# cable_with_five_imu.net
KiCad netlist of a schematic drawn in EAGLE
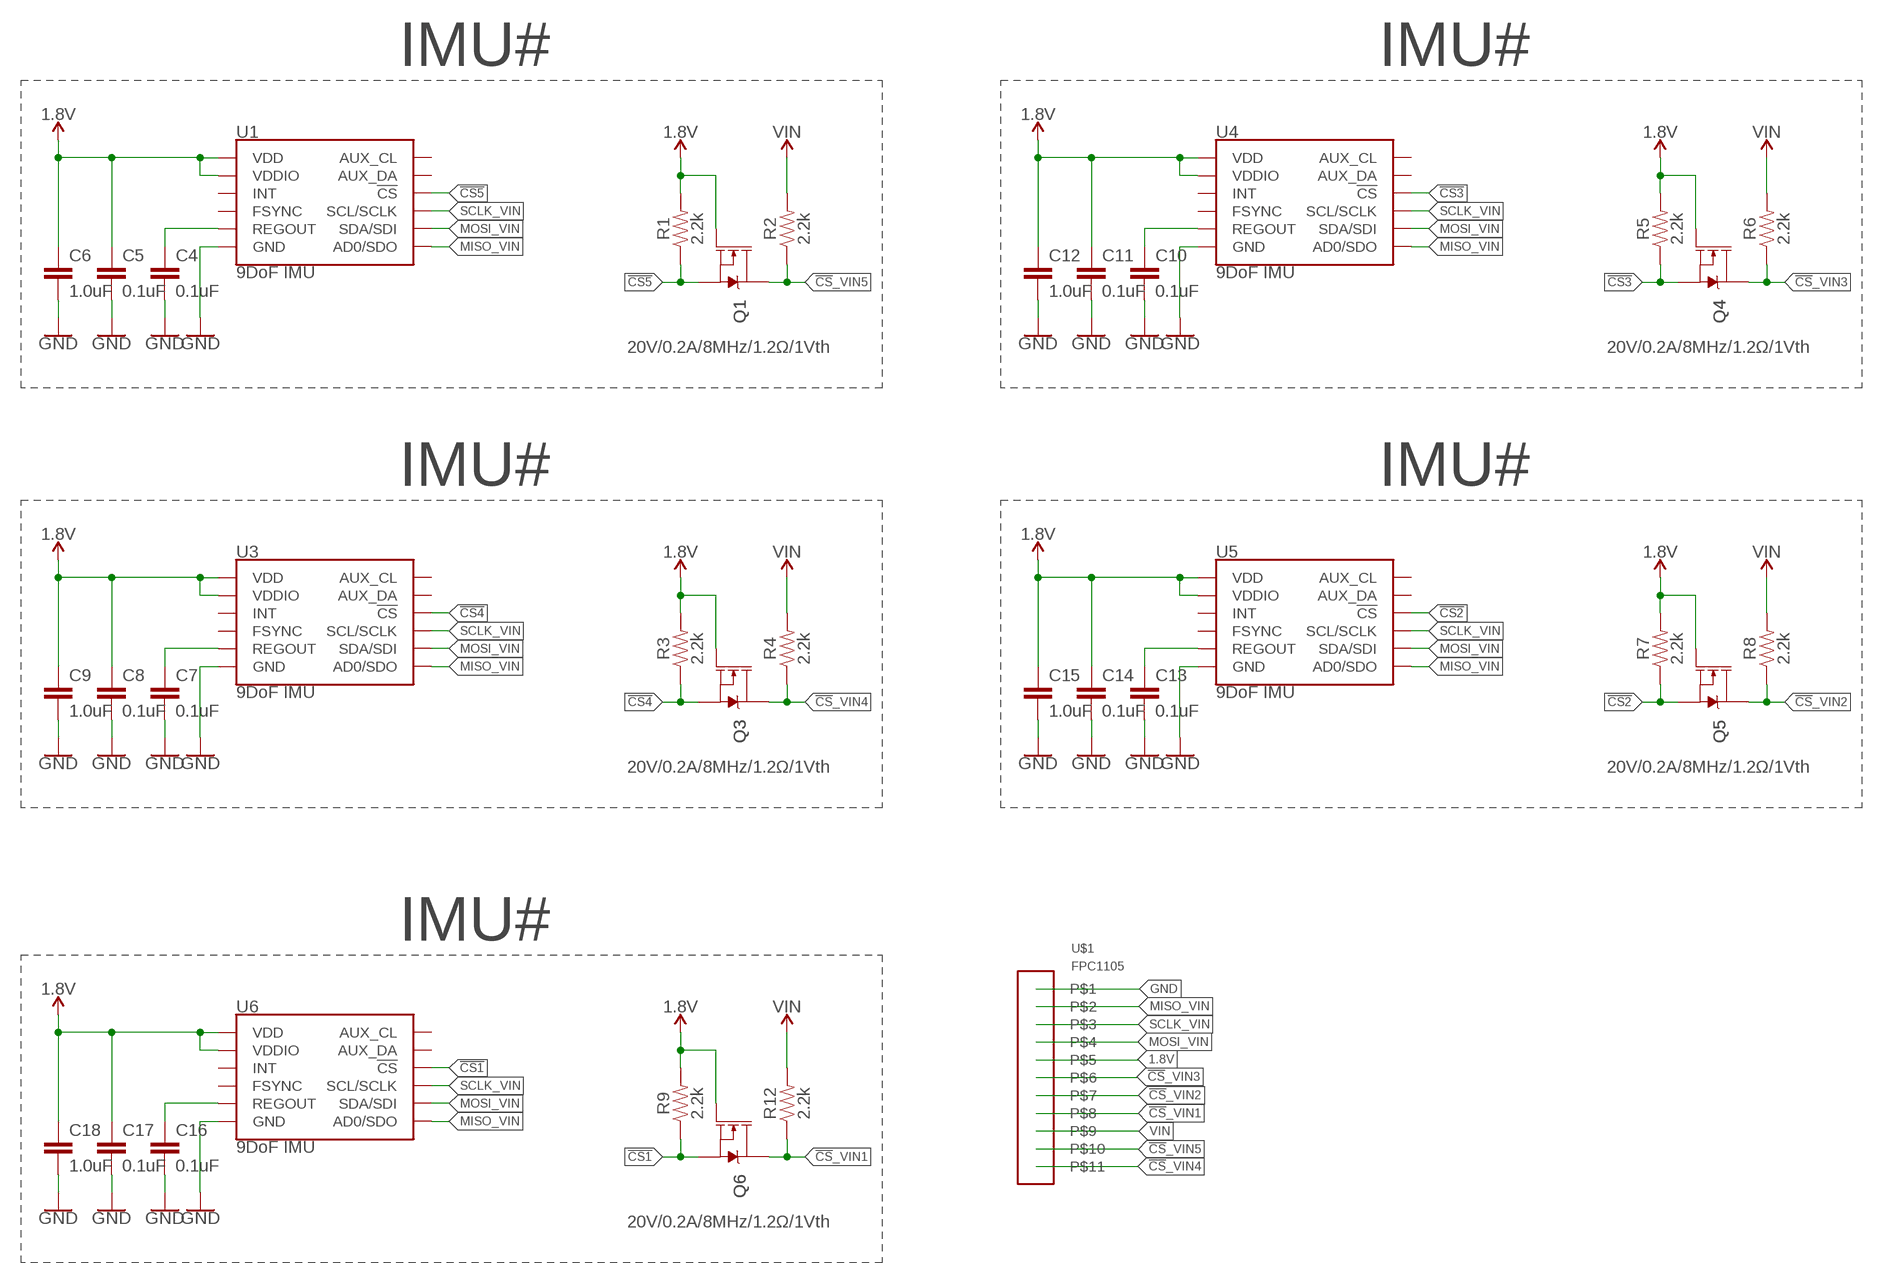
[diagram p0: schematic, sheet 1]

(export (version "E")
  (design (tool "Eeschema 10.0.6"))
  (components
    (comp (ref "C4")
      (value "0.1uF")
      (footprint "eagle-import:0603")
      (libsource (lib "eagle-import") (part "0.1UF-0603-25V-5%"))
    )
    (comp (ref "C5")
      (value "0.1uF")
      (footprint "eagle-import:0603")
      (libsource (lib "eagle-import") (part "0.1UF-0603-25V-5%"))
    )
    (comp (ref "C6")
      (value "1.0uF")
      (footprint "eagle-import:0603")
      (libsource (lib "eagle-import") (part "1.0UF-0603-16V-10%-X7R"))
    )
    (comp (ref "C7")
      (value "0.1uF")
      (footprint "eagle-import:0603")
      (libsource (lib "eagle-import") (part "0.1UF-0603-25V-5%"))
    )
    (comp (ref "C8")
      (value "0.1uF")
      (footprint "eagle-import:0603")
      (libsource (lib "eagle-import") (part "0.1UF-0603-25V-5%"))
    )
    (comp (ref "C9")
      (value "1.0uF")
      (footprint "eagle-import:0603")
      (libsource (lib "eagle-import") (part "1.0UF-0603-16V-10%-X7R"))
    )
    (comp (ref "C10")
      (value "0.1uF")
      (footprint "eagle-import:0603")
      (libsource (lib "eagle-import") (part "0.1UF-0603-25V-5%"))
    )
    (comp (ref "C11")
      (value "0.1uF")
      (footprint "eagle-import:0603")
      (libsource (lib "eagle-import") (part "0.1UF-0603-25V-5%"))
    )
    (comp (ref "C12")
      (value "1.0uF")
      (footprint "eagle-import:0603")
      (libsource (lib "eagle-import") (part "1.0UF-0603-16V-10%-X7R"))
    )
    (comp (ref "C13")
      (value "0.1uF")
      (footprint "eagle-import:0603")
      (libsource (lib "eagle-import") (part "0.1UF-0603-25V-5%"))
    )
    (comp (ref "C14")
      (value "0.1uF")
      (footprint "eagle-import:0603")
      (libsource (lib "eagle-import") (part "0.1UF-0603-25V-5%"))
    )
    (comp (ref "C15")
      (value "1.0uF")
      (footprint "eagle-import:0603")
      (libsource (lib "eagle-import") (part "1.0UF-0603-16V-10%-X7R"))
    )
    (comp (ref "C16")
      (value "0.1uF")
      (footprint "eagle-import:0603")
      (libsource (lib "eagle-import") (part "0.1UF-0603-25V-5%"))
    )
    (comp (ref "C17")
      (value "0.1uF")
      (footprint "eagle-import:0603")
      (libsource (lib "eagle-import") (part "0.1UF-0603-25V-5%"))
    )
    (comp (ref "C18")
      (value "1.0uF")
      (footprint "eagle-import:0603")
      (libsource (lib "eagle-import") (part "1.0UF-0603-16V-10%-X7R"))
    )
    (comp (ref "Q1")
      (value "20V/0.2A/8MHz/1.2Ω/1Vth")
      (footprint "eagle-import:SOT-416FL")
      (libsource (lib "eagle-import") (part "MOSFET-NCH-RE1C002UN"))
    )
    (comp (ref "Q3")
      (value "20V/0.2A/8MHz/1.2Ω/1Vth")
      (footprint "eagle-import:SOT-416FL")
      (libsource (lib "eagle-import") (part "MOSFET-NCH-RE1C002UN"))
    )
    (comp (ref "Q4")
      (value "20V/0.2A/8MHz/1.2Ω/1Vth")
      (footprint "eagle-import:SOT-416FL")
      (libsource (lib "eagle-import") (part "MOSFET-NCH-RE1C002UN"))
    )
    (comp (ref "Q5")
      (value "20V/0.2A/8MHz/1.2Ω/1Vth")
      (footprint "eagle-import:SOT-416FL")
      (libsource (lib "eagle-import") (part "MOSFET-NCH-RE1C002UN"))
    )
    (comp (ref "Q6")
      (value "20V/0.2A/8MHz/1.2Ω/1Vth")
      (footprint "eagle-import:SOT-416FL")
      (libsource (lib "eagle-import") (part "MOSFET-NCH-RE1C002UN"))
    )
    (comp (ref "R1")
      (value "2.2k")
      (footprint "eagle-import:0402-TIGHT")
      (libsource (lib "eagle-import") (part "2.2KOHM-0402T-1/16W-1%"))
    )
    (comp (ref "R2")
      (value "2.2k")
      (footprint "eagle-import:0402-TIGHT")
      (libsource (lib "eagle-import") (part "2.2KOHM-0402T-1/16W-1%"))
    )
    (comp (ref "R3")
      (value "2.2k")
      (footprint "eagle-import:0402-TIGHT")
      (libsource (lib "eagle-import") (part "2.2KOHM-0402T-1/16W-1%"))
    )
    (comp (ref "R4")
      (value "2.2k")
      (footprint "eagle-import:0402-TIGHT")
      (libsource (lib "eagle-import") (part "2.2KOHM-0402T-1/16W-1%"))
    )
    (comp (ref "R5")
      (value "2.2k")
      (footprint "eagle-import:0402-TIGHT")
      (libsource (lib "eagle-import") (part "2.2KOHM-0402T-1/16W-1%"))
    )
    (comp (ref "R6")
      (value "2.2k")
      (footprint "eagle-import:0402-TIGHT")
      (libsource (lib "eagle-import") (part "2.2KOHM-0402T-1/16W-1%"))
    )
    (comp (ref "R7")
      (value "2.2k")
      (footprint "eagle-import:0402-TIGHT")
      (libsource (lib "eagle-import") (part "2.2KOHM-0402T-1/16W-1%"))
    )
    (comp (ref "R8")
      (value "2.2k")
      (footprint "eagle-import:0402-TIGHT")
      (libsource (lib "eagle-import") (part "2.2KOHM-0402T-1/16W-1%"))
    )
    (comp (ref "R9")
      (value "2.2k")
      (footprint "eagle-import:0402-TIGHT")
      (libsource (lib "eagle-import") (part "2.2KOHM-0402T-1/16W-1%"))
    )
    (comp (ref "R12")
      (value "2.2k")
      (footprint "eagle-import:0402-TIGHT")
      (libsource (lib "eagle-import") (part "2.2KOHM-0402T-1/16W-1%"))
    )
    (comp (ref "U$1")
      (value "FPC1105")
      (footprint "eagle-import:FPC1105")
      (libsource (lib "eagle-import") (part "FPC1105"))
    )
    (comp (ref "U1")
      (value "9DoF IMU")
      (footprint "eagle-import:QFN24-3X3")
      (libsource (lib "eagle-import") (part "ICM-20948"))
    )
    (comp (ref "U3")
      (value "9DoF IMU")
      (footprint "eagle-import:QFN24-3X3")
      (libsource (lib "eagle-import") (part "ICM-20948"))
    )
    (comp (ref "U4")
      (value "9DoF IMU")
      (footprint "eagle-import:QFN24-3X3")
      (libsource (lib "eagle-import") (part "ICM-20948"))
    )
    (comp (ref "U5")
      (value "9DoF IMU")
      (footprint "eagle-import:QFN24-3X3")
      (libsource (lib "eagle-import") (part "ICM-20948"))
    )
    (comp (ref "U6")
      (value "9DoF IMU")
      (footprint "eagle-import:QFN24-3X3")
      (libsource (lib "eagle-import") (part "ICM-20948"))
    )
  )
  (nets
    (net (code "1") (name "/~{CS1}") (class "Default")
      (node (ref "Q6") (pin "2") (pinfunction "S_2") (pintype "bidirectional"))
      (node (ref "R9") (pin "1") (pinfunction "1_1") (pintype "passive"))
      (node (ref "U6") (pin "22") (pinfunction "~{CS}_22") (pintype "bidirectional"))
    )
    (net (code "2") (name "/~{CS2}") (class "Default")
      (node (ref "Q5") (pin "2") (pinfunction "S_2") (pintype "bidirectional"))
      (node (ref "R7") (pin "1") (pinfunction "1_1") (pintype "passive"))
      (node (ref "U5") (pin "22") (pinfunction "~{CS}_22") (pintype "bidirectional"))
    )
    (net (code "3") (name "/~{CS3}") (class "Default")
      (node (ref "Q4") (pin "2") (pinfunction "S_2") (pintype "bidirectional"))
      (node (ref "R5") (pin "1") (pinfunction "1_1") (pintype "passive"))
      (node (ref "U4") (pin "22") (pinfunction "~{CS}_22") (pintype "bidirectional"))
    )
    (net (code "4") (name "/~{CS4}") (class "Default")
      (node (ref "Q3") (pin "2") (pinfunction "S_2") (pintype "bidirectional"))
      (node (ref "R3") (pin "1") (pinfunction "1_1") (pintype "passive"))
      (node (ref "U3") (pin "22") (pinfunction "~{CS}_22") (pintype "bidirectional"))
    )
    (net (code "5") (name "/~{CS5}") (class "Default")
      (node (ref "Q1") (pin "2") (pinfunction "S_2") (pintype "bidirectional"))
      (node (ref "R1") (pin "1") (pinfunction "1_1") (pintype "passive"))
      (node (ref "U1") (pin "22") (pinfunction "~{CS}_22") (pintype "bidirectional"))
    )
    (net (code "6") (name "/~{CS}_VIN1") (class "Default")
      (node (ref "Q6") (pin "3") (pinfunction "D_3") (pintype "bidirectional"))
      (node (ref "R12") (pin "1") (pinfunction "1_1") (pintype "passive"))
      (node (ref "U$1") (pin "P$8") (pinfunction "P$8_P$8") (pintype "bidirectional"))
    )
    (net (code "7") (name "/~{CS}_VIN2") (class "Default")
      (node (ref "Q5") (pin "3") (pinfunction "D_3") (pintype "bidirectional"))
      (node (ref "R8") (pin "1") (pinfunction "1_1") (pintype "passive"))
      (node (ref "U$1") (pin "P$7") (pinfunction "P$7_P$7") (pintype "bidirectional"))
    )
    (net (code "8") (name "/~{CS}_VIN3") (class "Default")
      (node (ref "Q4") (pin "3") (pinfunction "D_3") (pintype "bidirectional"))
      (node (ref "R6") (pin "1") (pinfunction "1_1") (pintype "passive"))
      (node (ref "U$1") (pin "P$6") (pinfunction "P$6_P$6") (pintype "bidirectional"))
    )
    (net (code "9") (name "/~{CS}_VIN4") (class "Default")
      (node (ref "Q3") (pin "3") (pinfunction "D_3") (pintype "bidirectional"))
      (node (ref "R4") (pin "1") (pinfunction "1_1") (pintype "passive"))
      (node (ref "U$1") (pin "P$11") (pinfunction "P$11_P$11") (pintype "bidirectional"))
    )
    (net (code "10") (name "/~{CS}_VIN5") (class "Default")
      (node (ref "Q1") (pin "3") (pinfunction "D_3") (pintype "bidirectional"))
      (node (ref "R2") (pin "1") (pinfunction "1_1") (pintype "passive"))
      (node (ref "U$1") (pin "P$10") (pinfunction "P$10_P$10") (pintype "bidirectional"))
    )
    (net (code "11") (name "1.8V") (class "Default")
      (node (ref "C11") (pin "1") (pinfunction "1_1") (pintype "passive"))
      (node (ref "C12") (pin "1") (pinfunction "1_1") (pintype "passive"))
      (node (ref "C14") (pin "1") (pinfunction "1_1") (pintype "passive"))
      (node (ref "C15") (pin "1") (pinfunction "1_1") (pintype "passive"))
      (node (ref "C17") (pin "1") (pinfunction "1_1") (pintype "passive"))
      (node (ref "C18") (pin "1") (pinfunction "1_1") (pintype "passive"))
      (node (ref "C5") (pin "1") (pinfunction "1_1") (pintype "passive"))
      (node (ref "C6") (pin "1") (pinfunction "1_1") (pintype "passive"))
      (node (ref "C8") (pin "1") (pinfunction "1_1") (pintype "passive"))
      (node (ref "C9") (pin "1") (pinfunction "1_1") (pintype "passive"))
      (node (ref "Q1") (pin "1") (pinfunction "G_1") (pintype "bidirectional"))
      (node (ref "Q3") (pin "1") (pinfunction "G_1") (pintype "bidirectional"))
      (node (ref "Q4") (pin "1") (pinfunction "G_1") (pintype "bidirectional"))
      (node (ref "Q5") (pin "1") (pinfunction "G_1") (pintype "bidirectional"))
      (node (ref "Q6") (pin "1") (pinfunction "G_1") (pintype "bidirectional"))
      (node (ref "R1") (pin "2") (pinfunction "2_2") (pintype "passive"))
      (node (ref "R3") (pin "2") (pinfunction "2_2") (pintype "passive"))
      (node (ref "R5") (pin "2") (pinfunction "2_2") (pintype "passive"))
      (node (ref "R7") (pin "2") (pinfunction "2_2") (pintype "passive"))
      (node (ref "R9") (pin "2") (pinfunction "2_2") (pintype "passive"))
      (node (ref "U$1") (pin "P$5") (pinfunction "P$5_P$5") (pintype "bidirectional"))
      (node (ref "U1") (pin "13") (pinfunction "VDD_13") (pintype "bidirectional"))
      (node (ref "U1") (pin "8") (pinfunction "VDDIO_8") (pintype "bidirectional"))
      (node (ref "U3") (pin "13") (pinfunction "VDD_13") (pintype "bidirectional"))
      (node (ref "U3") (pin "8") (pinfunction "VDDIO_8") (pintype "bidirectional"))
      (node (ref "U4") (pin "13") (pinfunction "VDD_13") (pintype "bidirectional"))
      (node (ref "U4") (pin "8") (pinfunction "VDDIO_8") (pintype "bidirectional"))
      (node (ref "U5") (pin "13") (pinfunction "VDD_13") (pintype "bidirectional"))
      (node (ref "U5") (pin "8") (pinfunction "VDDIO_8") (pintype "bidirectional"))
      (node (ref "U6") (pin "13") (pinfunction "VDD_13") (pintype "bidirectional"))
      (node (ref "U6") (pin "8") (pinfunction "VDDIO_8") (pintype "bidirectional"))
    )
    (net (code "12") (name "GND") (class "Default")
      (node (ref "C10") (pin "2") (pinfunction "2_2") (pintype "passive"))
      (node (ref "C11") (pin "2") (pinfunction "2_2") (pintype "passive"))
      (node (ref "C12") (pin "2") (pinfunction "2_2") (pintype "passive"))
      (node (ref "C13") (pin "2") (pinfunction "2_2") (pintype "passive"))
      (node (ref "C14") (pin "2") (pinfunction "2_2") (pintype "passive"))
      (node (ref "C15") (pin "2") (pinfunction "2_2") (pintype "passive"))
      (node (ref "C16") (pin "2") (pinfunction "2_2") (pintype "passive"))
      (node (ref "C17") (pin "2") (pinfunction "2_2") (pintype "passive"))
      (node (ref "C18") (pin "2") (pinfunction "2_2") (pintype "passive"))
      (node (ref "C4") (pin "2") (pinfunction "2_2") (pintype "passive"))
      (node (ref "C5") (pin "2") (pinfunction "2_2") (pintype "passive"))
      (node (ref "C6") (pin "2") (pinfunction "2_2") (pintype "passive"))
      (node (ref "C7") (pin "2") (pinfunction "2_2") (pintype "passive"))
      (node (ref "C8") (pin "2") (pinfunction "2_2") (pintype "passive"))
      (node (ref "C9") (pin "2") (pinfunction "2_2") (pintype "passive"))
      (node (ref "U$1") (pin "P$1") (pinfunction "P$1_P$1") (pintype "bidirectional"))
      (node (ref "U1") (pin "18") (pinfunction "GND_18") (pintype "bidirectional"))
      (node (ref "U1") (pin "20") (pinfunction "GND_20") (pintype "bidirectional"))
      (node (ref "U3") (pin "18") (pinfunction "GND_18") (pintype "bidirectional"))
      (node (ref "U3") (pin "20") (pinfunction "GND_20") (pintype "bidirectional"))
      (node (ref "U4") (pin "18") (pinfunction "GND_18") (pintype "bidirectional"))
      (node (ref "U4") (pin "20") (pinfunction "GND_20") (pintype "bidirectional"))
      (node (ref "U5") (pin "18") (pinfunction "GND_18") (pintype "bidirectional"))
      (node (ref "U5") (pin "20") (pinfunction "GND_20") (pintype "bidirectional"))
      (node (ref "U6") (pin "18") (pinfunction "GND_18") (pintype "bidirectional"))
      (node (ref "U6") (pin "20") (pinfunction "GND_20") (pintype "bidirectional"))
    )
    (net (code "13") (name "MISO_VIN") (class "Default")
      (node (ref "U$1") (pin "P$2") (pinfunction "P$2_P$2") (pintype "bidirectional"))
      (node (ref "U1") (pin "9") (pinfunction "AD0/SDO_9") (pintype "bidirectional"))
      (node (ref "U3") (pin "9") (pinfunction "AD0/SDO_9") (pintype "bidirectional"))
      (node (ref "U4") (pin "9") (pinfunction "AD0/SDO_9") (pintype "bidirectional"))
      (node (ref "U5") (pin "9") (pinfunction "AD0/SDO_9") (pintype "bidirectional"))
      (node (ref "U6") (pin "9") (pinfunction "AD0/SDO_9") (pintype "bidirectional"))
    )
    (net (code "14") (name "MOSI_VIN") (class "Default")
      (node (ref "U$1") (pin "P$4") (pinfunction "P$4_P$4") (pintype "bidirectional"))
      (node (ref "U1") (pin "24") (pinfunction "SDA/SDI_24") (pintype "bidirectional"))
      (node (ref "U3") (pin "24") (pinfunction "SDA/SDI_24") (pintype "bidirectional"))
      (node (ref "U4") (pin "24") (pinfunction "SDA/SDI_24") (pintype "bidirectional"))
      (node (ref "U5") (pin "24") (pinfunction "SDA/SDI_24") (pintype "bidirectional"))
      (node (ref "U6") (pin "24") (pinfunction "SDA/SDI_24") (pintype "bidirectional"))
    )
    (net (code "15") (name "Net-(U1-REGOUT)") (class "Default")
      (node (ref "C4") (pin "1") (pinfunction "1_1") (pintype "passive"))
      (node (ref "U1") (pin "10") (pinfunction "REGOUT_10") (pintype "bidirectional"))
    )
    (net (code "16") (name "Net-(U3-REGOUT)") (class "Default")
      (node (ref "C7") (pin "1") (pinfunction "1_1") (pintype "passive"))
      (node (ref "U3") (pin "10") (pinfunction "REGOUT_10") (pintype "bidirectional"))
    )
    (net (code "17") (name "Net-(U4-REGOUT)") (class "Default")
      (node (ref "C10") (pin "1") (pinfunction "1_1") (pintype "passive"))
      (node (ref "U4") (pin "10") (pinfunction "REGOUT_10") (pintype "bidirectional"))
    )
    (net (code "18") (name "Net-(U5-REGOUT)") (class "Default")
      (node (ref "C13") (pin "1") (pinfunction "1_1") (pintype "passive"))
      (node (ref "U5") (pin "10") (pinfunction "REGOUT_10") (pintype "bidirectional"))
    )
    (net (code "19") (name "Net-(U6-REGOUT)") (class "Default")
      (node (ref "C16") (pin "1") (pinfunction "1_1") (pintype "passive"))
      (node (ref "U6") (pin "10") (pinfunction "REGOUT_10") (pintype "bidirectional"))
    )
    (net (code "20") (name "SCLK_VIN") (class "Default")
      (node (ref "U$1") (pin "P$3") (pinfunction "P$3_P$3") (pintype "bidirectional"))
      (node (ref "U1") (pin "23") (pinfunction "SCL/SCLK_23") (pintype "bidirectional"))
      (node (ref "U3") (pin "23") (pinfunction "SCL/SCLK_23") (pintype "bidirectional"))
      (node (ref "U4") (pin "23") (pinfunction "SCL/SCLK_23") (pintype "bidirectional"))
      (node (ref "U5") (pin "23") (pinfunction "SCL/SCLK_23") (pintype "bidirectional"))
      (node (ref "U6") (pin "23") (pinfunction "SCL/SCLK_23") (pintype "bidirectional"))
    )
    (net (code "21") (name "VIN") (class "Default")
      (node (ref "R12") (pin "2") (pinfunction "2_2") (pintype "passive"))
      (node (ref "R2") (pin "2") (pinfunction "2_2") (pintype "passive"))
      (node (ref "R4") (pin "2") (pinfunction "2_2") (pintype "passive"))
      (node (ref "R6") (pin "2") (pinfunction "2_2") (pintype "passive"))
      (node (ref "R8") (pin "2") (pinfunction "2_2") (pintype "passive"))
      (node (ref "U$1") (pin "P$9") (pinfunction "P$9_P$9") (pintype "bidirectional"))
    )
    (net (code "22") (name "unconnected-(U1-AUX_CL-Pad7)") (class "Default")
      (node (ref "U1") (pin "7") (pinfunction "AUX_CL_7") (pintype "bidirectional"))
    )
    (net (code "23") (name "unconnected-(U1-AUX_DA-Pad21)") (class "Default")
      (node (ref "U1") (pin "21") (pinfunction "AUX_DA_21") (pintype "bidirectional"))
    )
    (net (code "24") (name "unconnected-(U1-FSYNC-Pad11)") (class "Default")
      (node (ref "U1") (pin "11") (pinfunction "FSYNC_11") (pintype "bidirectional"))
    )
    (net (code "25") (name "unconnected-(U1-INT-Pad12)") (class "Default")
      (node (ref "U1") (pin "12") (pinfunction "INT_12") (pintype "bidirectional"))
    )
    (net (code "26") (name "unconnected-(U3-AUX_CL-Pad7)") (class "Default")
      (node (ref "U3") (pin "7") (pinfunction "AUX_CL_7") (pintype "bidirectional"))
    )
    (net (code "27") (name "unconnected-(U3-AUX_DA-Pad21)") (class "Default")
      (node (ref "U3") (pin "21") (pinfunction "AUX_DA_21") (pintype "bidirectional"))
    )
    (net (code "28") (name "unconnected-(U3-FSYNC-Pad11)") (class "Default")
      (node (ref "U3") (pin "11") (pinfunction "FSYNC_11") (pintype "bidirectional"))
    )
    (net (code "29") (name "unconnected-(U3-INT-Pad12)") (class "Default")
      (node (ref "U3") (pin "12") (pinfunction "INT_12") (pintype "bidirectional"))
    )
    (net (code "30") (name "unconnected-(U4-AUX_CL-Pad7)") (class "Default")
      (node (ref "U4") (pin "7") (pinfunction "AUX_CL_7") (pintype "bidirectional"))
    )
    (net (code "31") (name "unconnected-(U4-AUX_DA-Pad21)") (class "Default")
      (node (ref "U4") (pin "21") (pinfunction "AUX_DA_21") (pintype "bidirectional"))
    )
    (net (code "32") (name "unconnected-(U4-FSYNC-Pad11)") (class "Default")
      (node (ref "U4") (pin "11") (pinfunction "FSYNC_11") (pintype "bidirectional"))
    )
    (net (code "33") (name "unconnected-(U4-INT-Pad12)") (class "Default")
      (node (ref "U4") (pin "12") (pinfunction "INT_12") (pintype "bidirectional"))
    )
    (net (code "34") (name "unconnected-(U5-AUX_CL-Pad7)") (class "Default")
      (node (ref "U5") (pin "7") (pinfunction "AUX_CL_7") (pintype "bidirectional"))
    )
    (net (code "35") (name "unconnected-(U5-AUX_DA-Pad21)") (class "Default")
      (node (ref "U5") (pin "21") (pinfunction "AUX_DA_21") (pintype "bidirectional"))
    )
    (net (code "36") (name "unconnected-(U5-FSYNC-Pad11)") (class "Default")
      (node (ref "U5") (pin "11") (pinfunction "FSYNC_11") (pintype "bidirectional"))
    )
    (net (code "37") (name "unconnected-(U5-INT-Pad12)") (class "Default")
      (node (ref "U5") (pin "12") (pinfunction "INT_12") (pintype "bidirectional"))
    )
    (net (code "38") (name "unconnected-(U6-AUX_CL-Pad7)") (class "Default")
      (node (ref "U6") (pin "7") (pinfunction "AUX_CL_7") (pintype "bidirectional"))
    )
    (net (code "39") (name "unconnected-(U6-AUX_DA-Pad21)") (class "Default")
      (node (ref "U6") (pin "21") (pinfunction "AUX_DA_21") (pintype "bidirectional"))
    )
    (net (code "40") (name "unconnected-(U6-FSYNC-Pad11)") (class "Default")
      (node (ref "U6") (pin "11") (pinfunction "FSYNC_11") (pintype "bidirectional"))
    )
    (net (code "41") (name "unconnected-(U6-INT-Pad12)") (class "Default")
      (node (ref "U6") (pin "12") (pinfunction "INT_12") (pintype "bidirectional"))
    )
  )
)
